# AnalogShield-03.net
KiCad netlist of a schematic drawn in EAGLE
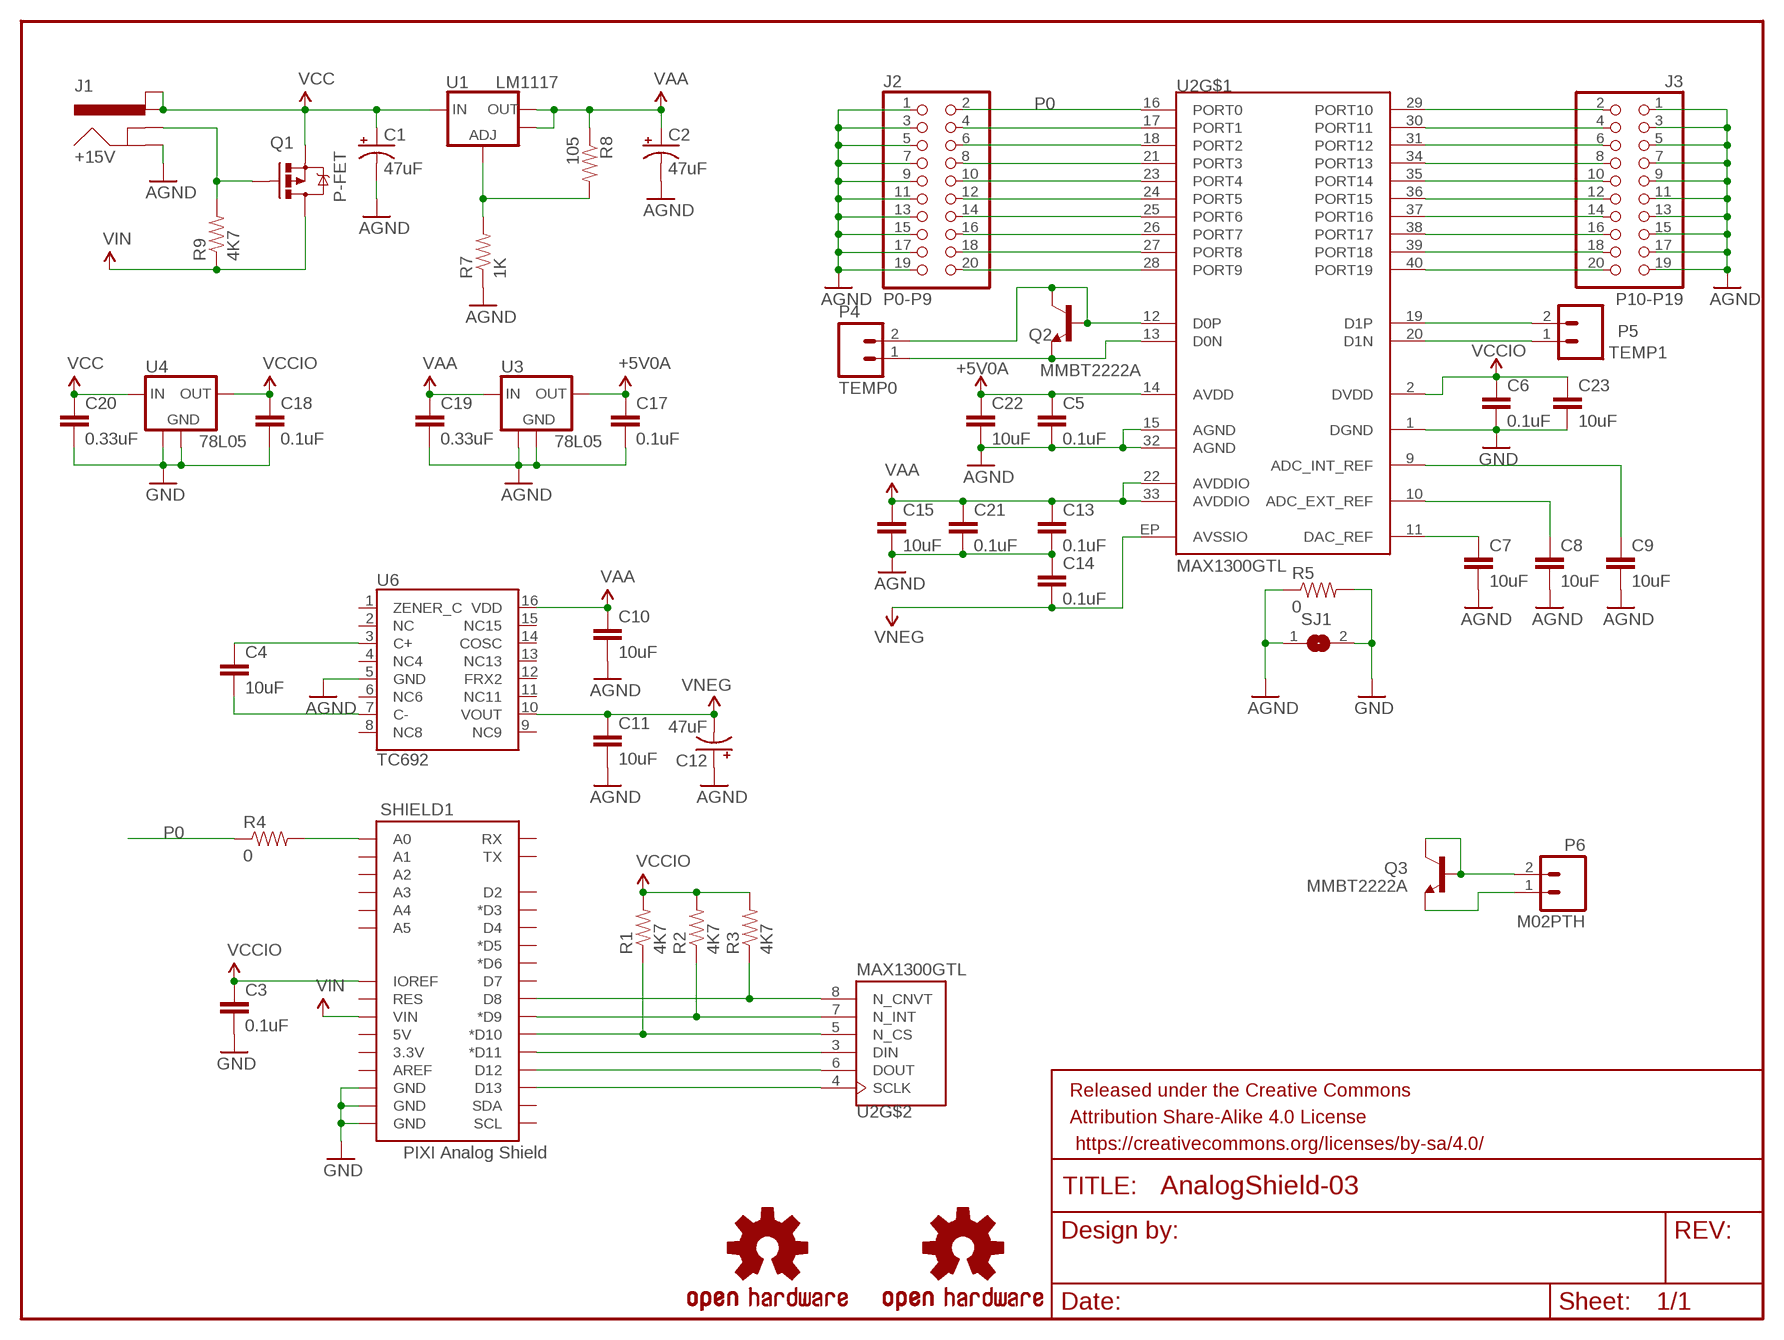
[diagram p0: schematic, sheet 1]

(export (version "E")
  (design (tool "Eeschema 10.0.6"))
  (components
    (comp (ref "C1")
      (value "47uF")
      (footprint "eagle-import:PANASONIC_D")
      (libsource (lib "eagle-import") (part "47UF-50V-20%(ELECT)"))
    )
    (comp (ref "C2")
      (value "47uF")
      (footprint "eagle-import:PANASONIC_D")
      (libsource (lib "eagle-import") (part "47UF-50V-20%(ELECT)"))
    )
    (comp (ref "C3")
      (value "0.1uF")
      (footprint "eagle-import:0603-CAP")
      (libsource (lib "eagle-import") (part "0.1UF-25V(+80/-20%)(0603)"))
    )
    (comp (ref "C4")
      (value "10uF")
      (footprint "eagle-import:1206")
      (libsource (lib "eagle-import") (part "10UF-25V-10%(1206)"))
    )
    (comp (ref "C5")
      (value "0.1uF")
      (footprint "eagle-import:0603-CAP")
      (libsource (lib "eagle-import") (part "0.1UF-25V(+80/-20%)(0603)"))
    )
    (comp (ref "C6")
      (value "0.1uF")
      (footprint "eagle-import:0603-CAP")
      (libsource (lib "eagle-import") (part "0.1UF-25V(+80/-20%)(0603)"))
    )
    (comp (ref "C7")
      (value "10uF")
      (footprint "eagle-import:1206")
      (libsource (lib "eagle-import") (part "10UF-25V-10%(1206)"))
    )
    (comp (ref "C8")
      (value "10uF")
      (footprint "eagle-import:1206")
      (libsource (lib "eagle-import") (part "10UF-25V-10%(1206)"))
    )
    (comp (ref "C9")
      (value "10uF")
      (footprint "eagle-import:1206")
      (libsource (lib "eagle-import") (part "10UF-25V-10%(1206)"))
    )
    (comp (ref "C10")
      (value "10uF")
      (footprint "eagle-import:1206")
      (libsource (lib "eagle-import") (part "10UF-25V-10%(1206)"))
    )
    (comp (ref "C11")
      (value "10uF")
      (footprint "eagle-import:1206")
      (libsource (lib "eagle-import") (part "10UF-25V-10%(1206)"))
    )
    (comp (ref "C12")
      (value "47uF")
      (footprint "eagle-import:PANASONIC_D")
      (libsource (lib "eagle-import") (part "47UF-50V-20%(ELECT)"))
    )
    (comp (ref "C13")
      (value "0.1uF")
      (footprint "eagle-import:0603-CAP")
      (libsource (lib "eagle-import") (part "0.1UF-25V(+80/-20%)(0603)"))
    )
    (comp (ref "C14")
      (value "0.1uF")
      (footprint "eagle-import:0603-CAP")
      (libsource (lib "eagle-import") (part "0.1UF-25V(+80/-20%)(0603)"))
    )
    (comp (ref "C15")
      (value "10uF")
      (footprint "eagle-import:1206")
      (libsource (lib "eagle-import") (part "10UF-25V-10%(1206)"))
    )
    (comp (ref "C17")
      (value "0.1uF")
      (footprint "eagle-import:0603-CAP")
      (libsource (lib "eagle-import") (part "0.1UF-25V(+80/-20%)(0603)"))
    )
    (comp (ref "C18")
      (value "0.1uF")
      (footprint "eagle-import:0603-CAP")
      (libsource (lib "eagle-import") (part "0.1UF-25V(+80/-20%)(0603)"))
    )
    (comp (ref "C19")
      (value "0.33uF")
      (footprint "eagle-import:0603-CAP")
      (libsource (lib "eagle-import") (part "0.33UF-25V(+20/-20%)(0603)"))
    )
    (comp (ref "C20")
      (value "0.33uF")
      (footprint "eagle-import:0603-CAP")
      (libsource (lib "eagle-import") (part "0.33UF-25V(+20/-20%)(0603)"))
    )
    (comp (ref "C21")
      (value "0.1uF")
      (footprint "eagle-import:0603-CAP")
      (libsource (lib "eagle-import") (part "0.1UF-25V(+80/-20%)(0603)"))
    )
    (comp (ref "C22")
      (value "10uF")
      (footprint "eagle-import:1206")
      (libsource (lib "eagle-import") (part "10UF-25V-10%(1206)"))
    )
    (comp (ref "C23")
      (value "10uF")
      (footprint "eagle-import:1206")
      (libsource (lib "eagle-import") (part "10UF-25V-10%(1206)"))
    )
    (comp (ref "FRAME1")
      (value "FRAME-LETTER")
      (footprint "eagle-import:CREATIVE_COMMONS")
      (libsource (lib "eagle-import") (part "FRAME-LETTER"))
    )
    (comp (ref "J1")
      (value "+15V")
      (footprint "eagle-import:POWER_JACK_SMD")
      (libsource (lib "eagle-import") (part "POWER_JACKSMD"))
    )
    (comp (ref "J2")
      (value "P0-P9")
      (footprint "eagle-import:2X10_SMD")
      (libsource (lib "eagle-import") (part "PINHD-2X10_SMD"))
    )
    (comp (ref "J3")
      (value "P10-P19")
      (footprint "eagle-import:2X10_SMD")
      (libsource (lib "eagle-import") (part "PINHD-2X10_SMD"))
    )
    (comp (ref "LOGO1")
      (value "OSHW-LOGOS")
      (footprint "eagle-import:OSHW-LOGO-S")
      (libsource (lib "eagle-import") (part "OSHW-LOGOS"))
    )
    (comp (ref "LOGO2")
      (value "OSHW-LOGOS")
      (footprint "eagle-import:OSHW-LOGO-S")
      (libsource (lib "eagle-import") (part "OSHW-LOGOS"))
    )
    (comp (ref "P4")
      (value "TEMP0")
      (footprint "eagle-import:1X02")
      (libsource (lib "eagle-import") (part "SparkFun-Connectors_M02PTH"))
    )
    (comp (ref "P5")
      (value "TEMP1")
      (footprint "eagle-import:JST-2-SMD-VERT")
      (libsource (lib "eagle-import") (part "M024UCON-15767"))
    )
    (comp (ref "P6")
      (value "M02PTH")
      (footprint "eagle-import:1X02")
      (libsource (lib "eagle-import") (part "SparkFun-Connectors_M02PTH"))
    )
    (comp (ref "Q1")
      (value "P-FET")
      (footprint "eagle-import:SOT23-3")
      (libsource (lib "eagle-import") (part "P-FET"))
    )
    (comp (ref "Q2")
      (value "MMBT2222A")
      (footprint "eagle-import:SOT23-3")
      (libsource (lib "eagle-import") (part "TRANSISTOR_NPNMMBT2222A"))
    )
    (comp (ref "Q3")
      (value "MMBT2222A")
      (footprint "eagle-import:SOT23-3")
      (libsource (lib "eagle-import") (part "TRANSISTOR_NPNMMBT2222A"))
    )
    (comp (ref "R1")
      (value "4K7")
      (footprint "eagle-import:0603")
      (libsource (lib "eagle-import") (part "4.7KOHM1/10W1%(0603)"))
    )
    (comp (ref "R2")
      (value "4K7")
      (footprint "eagle-import:0603")
      (libsource (lib "eagle-import") (part "4.7KOHM1/10W1%(0603)"))
    )
    (comp (ref "R3")
      (value "4K7")
      (footprint "eagle-import:0603")
      (libsource (lib "eagle-import") (part "4.7KOHM1/10W1%(0603)"))
    )
    (comp (ref "R4")
      (value "0")
      (footprint "eagle-import:0603")
      (libsource (lib "eagle-import") (part "0OHM-1/10W-5%(0603)"))
    )
    (comp (ref "R5")
      (value "0")
      (footprint "eagle-import:0603")
      (libsource (lib "eagle-import") (part "0OHM-1/10W-5%(0603)"))
    )
    (comp (ref "R7")
      (value "1K")
      (footprint "eagle-import:0603-RES")
      (libsource (lib "eagle-import") (part "1KOHM-1/10W-1%(0603)"))
    )
    (comp (ref "R8")
      (value "105")
      (footprint "eagle-import:0603-RES")
      (libsource (lib "eagle-import") (part "105OHM-1/10W-1%(0603)"))
    )
    (comp (ref "R9")
      (value "4K7")
      (footprint "eagle-import:0603")
      (libsource (lib "eagle-import") (part "4.7KOHM1/10W1%(0603)"))
    )
    (comp (ref "SHIELD1")
      (value "PIXI Analog Shield")
      (footprint "eagle-import:UNO_R3_SHIELD_NOLABELS")
      (libsource (lib "eagle-import") (part "ARDUINO_R3_SHIELDNOLABELS"))
    )
    (comp (ref "SJ1") (value "SJ") (footprint "eagle-import:SJ") (libsource (lib "eagle-import") (part "SJ")))
    (comp (ref "U1")
      (value "LM1117")
      (footprint "eagle-import:SOT223")
      (libsource (lib "eagle-import") (part "V_REG_LM1117SOT223"))
    )
    (comp (ref "U2")
      (value "MAX1300GTL")
      (footprint "eagle-import:QFN50P600X600X75-41")
      (fields (field (name "MFR1") "Maxim") (field (name "MFR1PN") "MAX11300GTL+"))
      (libsource (lib "eagle-import") (part "MAX11300GTL"))
    )
    (comp (ref "U3")
      (value "78L05")
      (footprint "eagle-import:SOT89")
      (libsource (lib "eagle-import") (part "78L05"))
    )
    (comp (ref "U4")
      (value "78L05")
      (footprint "eagle-import:SOT89")
      (libsource (lib "eagle-import") (part "78L05"))
    )
    (comp (ref "U6")
      (value "TC692")
      (footprint "eagle-import:SO16L")
      (libsource (lib "eagle-import") (part "TC962COE"))
    )
  )
  (nets
    (net (code "1") (name "+5V0A") (class "Default")
      (node (ref "C17") (pin "1") (pinfunction "1_1") (pintype "passive"))
      (node (ref "C22") (pin "1") (pinfunction "1_1") (pintype "passive"))
      (node (ref "C5") (pin "1") (pinfunction "1_1") (pintype "passive"))
      (node (ref "U2") (pin "14") (pinfunction "AVDD_14") (pintype "power_in"))
      (node (ref "U3") (pin "1") (pinfunction "OUT_1") (pintype "power_in"))
    )
    (net (code "2") (name "/P0") (class "Default")
      (node (ref "J2") (pin "2") (pinfunction "2_2") (pintype "passive"))
      (node (ref "R4") (pin "1") (pinfunction "1_1") (pintype "passive"))
      (node (ref "U2") (pin "16") (pinfunction "PORT0_16") (pintype "bidirectional"))
    )
    (net (code "3") (name "AGND") (class "Default")
      (node (ref "C1") (pin "-") (pinfunction "-_-") (pintype "passive"))
      (node (ref "C10") (pin "2") (pinfunction "2_2") (pintype "passive"))
      (node (ref "C11") (pin "2") (pinfunction "2_2") (pintype "passive"))
      (node (ref "C12") (pin "+") (pinfunction "+_+") (pintype "passive"))
      (node (ref "C13") (pin "2") (pinfunction "2_2") (pintype "passive"))
      (node (ref "C14") (pin "1") (pinfunction "1_1") (pintype "passive"))
      (node (ref "C15") (pin "2") (pinfunction "2_2") (pintype "passive"))
      (node (ref "C17") (pin "2") (pinfunction "2_2") (pintype "passive"))
      (node (ref "C19") (pin "2") (pinfunction "2_2") (pintype "passive"))
      (node (ref "C2") (pin "-") (pinfunction "-_-") (pintype "passive"))
      (node (ref "C21") (pin "2") (pinfunction "2_2") (pintype "passive"))
      (node (ref "C22") (pin "2") (pinfunction "2_2") (pintype "passive"))
      (node (ref "C5") (pin "2") (pinfunction "2_2") (pintype "passive"))
      (node (ref "C7") (pin "2") (pinfunction "2_2") (pintype "passive"))
      (node (ref "C8") (pin "2") (pinfunction "2_2") (pintype "passive"))
      (node (ref "C9") (pin "2") (pinfunction "2_2") (pintype "passive"))
      (node (ref "J1") (pin "GND") (pinfunction "GND_GND") (pintype "bidirectional"))
      (node (ref "J2") (pin "1") (pinfunction "1_1") (pintype "passive"))
      (node (ref "J2") (pin "11") (pinfunction "11_11") (pintype "passive"))
      (node (ref "J2") (pin "13") (pinfunction "13_13") (pintype "passive"))
      (node (ref "J2") (pin "15") (pinfunction "15_15") (pintype "passive"))
      (node (ref "J2") (pin "17") (pinfunction "17_17") (pintype "passive"))
      (node (ref "J2") (pin "19") (pinfunction "19_19") (pintype "passive"))
      (node (ref "J2") (pin "3") (pinfunction "3_3") (pintype "passive"))
      (node (ref "J2") (pin "5") (pinfunction "5_5") (pintype "passive"))
      (node (ref "J2") (pin "7") (pinfunction "7_7") (pintype "passive"))
      (node (ref "J2") (pin "9") (pinfunction "9_9") (pintype "passive"))
      (node (ref "J3") (pin "1") (pinfunction "1_1") (pintype "passive"))
      (node (ref "J3") (pin "11") (pinfunction "11_11") (pintype "passive"))
      (node (ref "J3") (pin "13") (pinfunction "13_13") (pintype "passive"))
      (node (ref "J3") (pin "15") (pinfunction "15_15") (pintype "passive"))
      (node (ref "J3") (pin "17") (pinfunction "17_17") (pintype "passive"))
      (node (ref "J3") (pin "19") (pinfunction "19_19") (pintype "passive"))
      (node (ref "J3") (pin "3") (pinfunction "3_3") (pintype "passive"))
      (node (ref "J3") (pin "5") (pinfunction "5_5") (pintype "passive"))
      (node (ref "J3") (pin "7") (pinfunction "7_7") (pintype "passive"))
      (node (ref "J3") (pin "9") (pinfunction "9_9") (pintype "passive"))
      (node (ref "R5") (pin "1") (pinfunction "1_1") (pintype "passive"))
      (node (ref "R7") (pin "1") (pinfunction "1_1") (pintype "passive"))
      (node (ref "SJ1") (pin "1") (pinfunction "1_1") (pintype "passive"))
      (node (ref "U2") (pin "15") (pinfunction "AGND_15") (pintype "power_in"))
      (node (ref "U2") (pin "32") (pinfunction "AGND_32") (pintype "power_in"))
      (node (ref "U3") (pin "2") (pinfunction "GND_2") (pintype "power_in"))
      (node (ref "U3") (pin "4") (pinfunction "GND_4") (pintype "power_in"))
      (node (ref "U6") (pin "5") (pinfunction "GND_5") (pintype "bidirectional"))
    )
    (net (code "4") (name "GND") (class "Default")
      (node (ref "C18") (pin "2") (pinfunction "2_2") (pintype "passive"))
      (node (ref "C20") (pin "2") (pinfunction "2_2") (pintype "passive"))
      (node (ref "C23") (pin "2") (pinfunction "2_2") (pintype "passive"))
      (node (ref "C3") (pin "2") (pinfunction "2_2") (pintype "passive"))
      (node (ref "C6") (pin "2") (pinfunction "2_2") (pintype "passive"))
      (node (ref "R5") (pin "2") (pinfunction "2_2") (pintype "passive"))
      (node (ref "SHIELD1") (pin "GND@0") (pinfunction "GND_GND@0") (pintype "bidirectional"))
      (node (ref "SHIELD1") (pin "GND@1") (pinfunction "GND_GND@1") (pintype "bidirectional"))
      (node (ref "SHIELD1") (pin "GND@2") (pinfunction "GND_GND@2") (pintype "bidirectional"))
      (node (ref "SJ1") (pin "2") (pinfunction "2_2") (pintype "passive"))
      (node (ref "U2") (pin "1") (pinfunction "DGND_1") (pintype "power_in"))
      (node (ref "U4") (pin "2") (pinfunction "GND_2") (pintype "power_in"))
      (node (ref "U4") (pin "4") (pinfunction "GND_4") (pintype "power_in"))
    )
    (net (code "5") (name "Net-(J1-GNDBREAK)") (class "Default")
      (node (ref "J1") (pin "P$4") (pinfunction "GNDBREAK_P$4") (pintype "bidirectional"))
      (node (ref "Q1") (pin "1") (pinfunction "G_1") (pintype "passive"))
      (node (ref "R9") (pin "2") (pinfunction "2_2") (pintype "passive"))
    )
    (net (code "6") (name "Net-(P5-1)") (class "Default")
      (node (ref "P5") (pin "2") (pinfunction "1_2") (pintype "passive"))
      (node (ref "U2") (pin "19") (pinfunction "D1P_19") (pintype "passive"))
    )
    (net (code "7") (name "Net-(P5-2)") (class "Default")
      (node (ref "P5") (pin "1") (pinfunction "2_1") (pintype "passive"))
      (node (ref "U2") (pin "20") (pinfunction "D1N_20") (pintype "passive"))
    )
    (net (code "8") (name "Net-(Q2-B)") (class "Default")
      (node (ref "P4") (pin "2") (pinfunction "2_2") (pintype "passive"))
      (node (ref "Q2") (pin "1") (pinfunction "B_1") (pintype "passive"))
      (node (ref "Q2") (pin "3") (pinfunction "C_3") (pintype "passive"))
      (node (ref "U2") (pin "12") (pinfunction "D0P_12") (pintype "passive"))
    )
    (net (code "9") (name "Net-(Q2-E)") (class "Default")
      (node (ref "P4") (pin "1") (pinfunction "1_1") (pintype "passive"))
      (node (ref "Q2") (pin "2") (pinfunction "E_2") (pintype "passive"))
      (node (ref "U2") (pin "13") (pinfunction "D0N_13") (pintype "passive"))
    )
    (net (code "10") (name "Net-(Q3-B)") (class "Default")
      (node (ref "P6") (pin "2") (pinfunction "2_2") (pintype "passive"))
      (node (ref "Q3") (pin "1") (pinfunction "B_1") (pintype "passive"))
      (node (ref "Q3") (pin "3") (pinfunction "C_3") (pintype "passive"))
    )
    (net (code "11") (name "Net-(Q3-E)") (class "Default")
      (node (ref "P6") (pin "1") (pinfunction "1_1") (pintype "passive"))
      (node (ref "Q3") (pin "2") (pinfunction "E_2") (pintype "passive"))
    )
    (net (code "12") (name "Net-(R4-Pad2)") (class "Default")
      (node (ref "R4") (pin "2") (pinfunction "2_2") (pintype "passive"))
      (node (ref "SHIELD1") (pin "A0") (pinfunction "A0_A0") (pintype "bidirectional"))
    )
    (net (code "13") (name "Net-(SHIELD1-*D9)") (class "Default")
      (node (ref "R2") (pin "1") (pinfunction "1_1") (pintype "passive"))
      (node (ref "SHIELD1") (pin "D9") (pinfunction "*D9_D9") (pintype "bidirectional"))
      (node (ref "U2") (pin "7") (pinfunction "N_INT_7") (pintype "output"))
    )
    (net (code "14") (name "Net-(SHIELD1-*D10)") (class "Default")
      (node (ref "R1") (pin "1") (pinfunction "1_1") (pintype "passive"))
      (node (ref "SHIELD1") (pin "D10") (pinfunction "*D10_D10") (pintype "bidirectional"))
      (node (ref "U2") (pin "5") (pinfunction "N_CS_5") (pintype "input"))
    )
    (net (code "15") (name "Net-(SHIELD1-*D11)") (class "Default")
      (node (ref "SHIELD1") (pin "D11") (pinfunction "*D11_D11") (pintype "bidirectional"))
      (node (ref "U2") (pin "3") (pinfunction "DIN_3") (pintype "input"))
    )
    (net (code "16") (name "Net-(U1-ADJ)") (class "Default")
      (node (ref "R7") (pin "2") (pinfunction "2_2") (pintype "passive"))
      (node (ref "R8") (pin "2") (pinfunction "2_2") (pintype "passive"))
      (node (ref "U1") (pin "1") (pinfunction "ADJ_1") (pintype "input"))
    )
    (net (code "17") (name "Net-(U2A-ADC_EXT_REF)") (class "Default")
      (node (ref "C8") (pin "1") (pinfunction "1_1") (pintype "passive"))
      (node (ref "U2") (pin "10") (pinfunction "ADC_EXT_REF_10") (pintype "passive"))
    )
    (net (code "18") (name "Net-(U2A-ADC_INT_REF)") (class "Default")
      (node (ref "C9") (pin "1") (pinfunction "1_1") (pintype "passive"))
      (node (ref "U2") (pin "9") (pinfunction "ADC_INT_REF_9") (pintype "passive"))
    )
    (net (code "19") (name "Net-(U2A-DAC_REF)") (class "Default")
      (node (ref "C7") (pin "1") (pinfunction "1_1") (pintype "passive"))
      (node (ref "U2") (pin "11") (pinfunction "DAC_REF_11") (pintype "passive"))
    )
    (net (code "20") (name "Net-(U2A-PORT1)") (class "Default")
      (node (ref "J2") (pin "4") (pinfunction "4_4") (pintype "passive"))
      (node (ref "U2") (pin "17") (pinfunction "PORT1_17") (pintype "bidirectional"))
    )
    (net (code "21") (name "Net-(U2A-PORT2)") (class "Default")
      (node (ref "J2") (pin "6") (pinfunction "6_6") (pintype "passive"))
      (node (ref "U2") (pin "18") (pinfunction "PORT2_18") (pintype "bidirectional"))
    )
    (net (code "22") (name "Net-(U2A-PORT3)") (class "Default")
      (node (ref "J2") (pin "8") (pinfunction "8_8") (pintype "passive"))
      (node (ref "U2") (pin "21") (pinfunction "PORT3_21") (pintype "bidirectional"))
    )
    (net (code "23") (name "Net-(U2A-PORT4)") (class "Default")
      (node (ref "J2") (pin "10") (pinfunction "10_10") (pintype "passive"))
      (node (ref "U2") (pin "23") (pinfunction "PORT4_23") (pintype "bidirectional"))
    )
    (net (code "24") (name "Net-(U2A-PORT5)") (class "Default")
      (node (ref "J2") (pin "12") (pinfunction "12_12") (pintype "passive"))
      (node (ref "U2") (pin "24") (pinfunction "PORT5_24") (pintype "bidirectional"))
    )
    (net (code "25") (name "Net-(U2A-PORT6)") (class "Default")
      (node (ref "J2") (pin "14") (pinfunction "14_14") (pintype "passive"))
      (node (ref "U2") (pin "25") (pinfunction "PORT6_25") (pintype "bidirectional"))
    )
    (net (code "26") (name "Net-(U2A-PORT7)") (class "Default")
      (node (ref "J2") (pin "16") (pinfunction "16_16") (pintype "passive"))
      (node (ref "U2") (pin "26") (pinfunction "PORT7_26") (pintype "bidirectional"))
    )
    (net (code "27") (name "Net-(U2A-PORT8)") (class "Default")
      (node (ref "J2") (pin "18") (pinfunction "18_18") (pintype "passive"))
      (node (ref "U2") (pin "27") (pinfunction "PORT8_27") (pintype "bidirectional"))
    )
    (net (code "28") (name "Net-(U2A-PORT9)") (class "Default")
      (node (ref "J2") (pin "20") (pinfunction "20_20") (pintype "passive"))
      (node (ref "U2") (pin "28") (pinfunction "PORT9_28") (pintype "bidirectional"))
    )
    (net (code "29") (name "Net-(U2A-PORT10)") (class "Default")
      (node (ref "J3") (pin "2") (pinfunction "2_2") (pintype "passive"))
      (node (ref "U2") (pin "29") (pinfunction "PORT10_29") (pintype "bidirectional"))
    )
    (net (code "30") (name "Net-(U2A-PORT11)") (class "Default")
      (node (ref "J3") (pin "4") (pinfunction "4_4") (pintype "passive"))
      (node (ref "U2") (pin "30") (pinfunction "PORT11_30") (pintype "bidirectional"))
    )
    (net (code "31") (name "Net-(U2A-PORT12)") (class "Default")
      (node (ref "J3") (pin "6") (pinfunction "6_6") (pintype "passive"))
      (node (ref "U2") (pin "31") (pinfunction "PORT12_31") (pintype "bidirectional"))
    )
    (net (code "32") (name "Net-(U2A-PORT13)") (class "Default")
      (node (ref "J3") (pin "8") (pinfunction "8_8") (pintype "passive"))
      (node (ref "U2") (pin "34") (pinfunction "PORT13_34") (pintype "bidirectional"))
    )
    (net (code "33") (name "Net-(U2A-PORT14)") (class "Default")
      (node (ref "J3") (pin "10") (pinfunction "10_10") (pintype "passive"))
      (node (ref "U2") (pin "35") (pinfunction "PORT14_35") (pintype "bidirectional"))
    )
    (net (code "34") (name "Net-(U2A-PORT15)") (class "Default")
      (node (ref "J3") (pin "12") (pinfunction "12_12") (pintype "passive"))
      (node (ref "U2") (pin "36") (pinfunction "PORT15_36") (pintype "bidirectional"))
    )
    (net (code "35") (name "Net-(U2A-PORT16)") (class "Default")
      (node (ref "J3") (pin "14") (pinfunction "14_14") (pintype "passive"))
      (node (ref "U2") (pin "37") (pinfunction "PORT16_37") (pintype "bidirectional"))
    )
    (net (code "36") (name "Net-(U2A-PORT17)") (class "Default")
      (node (ref "J3") (pin "16") (pinfunction "16_16") (pintype "passive"))
      (node (ref "U2") (pin "38") (pinfunction "PORT17_38") (pintype "bidirectional"))
    )
    (net (code "37") (name "Net-(U2A-PORT18)") (class "Default")
      (node (ref "J3") (pin "18") (pinfunction "18_18") (pintype "passive"))
      (node (ref "U2") (pin "39") (pinfunction "PORT18_39") (pintype "bidirectional"))
    )
    (net (code "38") (name "Net-(U2A-PORT19)") (class "Default")
      (node (ref "J3") (pin "20") (pinfunction "20_20") (pintype "passive"))
      (node (ref "U2") (pin "40") (pinfunction "PORT19_40") (pintype "bidirectional"))
    )
    (net (code "39") (name "Net-(U2B-DOUT)") (class "Default")
      (node (ref "SHIELD1") (pin "D12") (pinfunction "D12_D12") (pintype "bidirectional"))
      (node (ref "U2") (pin "6") (pinfunction "DOUT_6") (pintype "output"))
    )
    (net (code "40") (name "Net-(U2B-N_CNVT)") (class "Default")
      (node (ref "R3") (pin "1") (pinfunction "1_1") (pintype "passive"))
      (node (ref "SHIELD1") (pin "D8") (pinfunction "D8_D8") (pintype "bidirectional"))
      (node (ref "U2") (pin "8") (pinfunction "N_CNVT_8") (pintype "input"))
    )
    (net (code "41") (name "Net-(U2B-SCLK)") (class "Default")
      (node (ref "SHIELD1") (pin "D13") (pinfunction "D13_D13") (pintype "bidirectional"))
      (node (ref "U2") (pin "4") (pinfunction "SCLK_4") (pintype "input"))
    )
    (net (code "42") (name "Net-(U6-C+)") (class "Default")
      (node (ref "C4") (pin "1") (pinfunction "1_1") (pintype "passive"))
      (node (ref "U6") (pin "3") (pinfunction "C+_3") (pintype "bidirectional"))
    )
    (net (code "43") (name "Net-(U6-C-)") (class "Default")
      (node (ref "C4") (pin "2") (pinfunction "2_2") (pintype "passive"))
      (node (ref "U6") (pin "7") (pinfunction "C-_7") (pintype "bidirectional"))
    )
    (net (code "44") (name "VAA") (class "Default")
      (node (ref "C10") (pin "1") (pinfunction "1_1") (pintype "passive"))
      (node (ref "C13") (pin "1") (pinfunction "1_1") (pintype "passive"))
      (node (ref "C15") (pin "1") (pinfunction "1_1") (pintype "passive"))
      (node (ref "C19") (pin "1") (pinfunction "1_1") (pintype "passive"))
      (node (ref "C2") (pin "+") (pinfunction "+_+") (pintype "passive"))
      (node (ref "C21") (pin "1") (pinfunction "1_1") (pintype "passive"))
      (node (ref "R8") (pin "1") (pinfunction "1_1") (pintype "passive"))
      (node (ref "U1") (pin "2") (pinfunction "OUT_2") (pintype "power_in"))
      (node (ref "U1") (pin "4") (pinfunction "OUT_4") (pintype "power_in"))
      (node (ref "U2") (pin "22") (pinfunction "AVDDIO_22") (pintype "power_in"))
      (node (ref "U2") (pin "33") (pinfunction "AVDDIO_33") (pintype "power_in"))
      (node (ref "U3") (pin "3") (pinfunction "IN_3") (pintype "input"))
      (node (ref "U6") (pin "16") (pinfunction "VDD_16") (pintype "bidirectional"))
    )
    (net (code "45") (name "VCC") (class "Default")
      (node (ref "C1") (pin "+") (pinfunction "+_+") (pintype "passive"))
      (node (ref "C20") (pin "1") (pinfunction "1_1") (pintype "passive"))
      (node (ref "J1") (pin "VIN0$1") (pinfunction "PWR_VIN0$1") (pintype "bidirectional"))
      (node (ref "J1") (pin "VIN0$2") (pinfunction "PWR1_VIN0$2") (pintype "bidirectional"))
      (node (ref "Q1") (pin "2") (pinfunction "S_2") (pintype "passive"))
      (node (ref "U1") (pin "3") (pinfunction "IN_3") (pintype "input"))
      (node (ref "U4") (pin "3") (pinfunction "IN_3") (pintype "input"))
    )
    (net (code "46") (name "VCCIO") (class "Default")
      (node (ref "C18") (pin "1") (pinfunction "1_1") (pintype "passive"))
      (node (ref "C23") (pin "1") (pinfunction "1_1") (pintype "passive"))
      (node (ref "C3") (pin "1") (pinfunction "1_1") (pintype "passive"))
      (node (ref "C6") (pin "1") (pinfunction "1_1") (pintype "passive"))
      (node (ref "R1") (pin "2") (pinfunction "2_2") (pintype "passive"))
      (node (ref "R2") (pin "2") (pinfunction "2_2") (pintype "passive"))
      (node (ref "R3") (pin "2") (pinfunction "2_2") (pintype "passive"))
      (node (ref "SHIELD1") (pin "IOREF") (pinfunction "IOREF_IOREF") (pintype "bidirectional"))
      (node (ref "U2") (pin "2") (pinfunction "DVDD_2") (pintype "power_in"))
      (node (ref "U4") (pin "1") (pinfunction "OUT_1") (pintype "power_in"))
    )
    (net (code "47") (name "VIN") (class "Default")
      (node (ref "Q1") (pin "3") (pinfunction "D_3") (pintype "passive"))
      (node (ref "R9") (pin "1") (pinfunction "1_1") (pintype "passive"))
      (node (ref "SHIELD1") (pin "VIN") (pinfunction "VIN_VIN") (pintype "bidirectional"))
    )
    (net (code "48") (name "VNEG") (class "Default")
      (node (ref "C11") (pin "1") (pinfunction "1_1") (pintype "passive"))
      (node (ref "C12") (pin "-") (pinfunction "-_-") (pintype "passive"))
      (node (ref "C14") (pin "2") (pinfunction "2_2") (pintype "passive"))
      (node (ref "U2") (pin "EP") (pinfunction "AVSSIO_EP") (pintype "power_in"))
      (node (ref "U6") (pin "10") (pinfunction "VOUT_10") (pintype "bidirectional"))
    )
    (net (code "49") (name "unconnected-(SHIELD1-*D3-PadD3)") (class "Default")
      (node (ref "SHIELD1") (pin "D3") (pinfunction "*D3_D3") (pintype "bidirectional"))
    )
    (net (code "50") (name "unconnected-(SHIELD1-*D5-PadD5)") (class "Default")
      (node (ref "SHIELD1") (pin "D5") (pinfunction "*D5_D5") (pintype "bidirectional"))
    )
    (net (code "51") (name "unconnected-(SHIELD1-*D6-PadD6)") (class "Default")
      (node (ref "SHIELD1") (pin "D6") (pinfunction "*D6_D6") (pintype "bidirectional"))
    )
    (net (code "52") (name "unconnected-(SHIELD1-Pad3.3V)") (class "Default")
      (node (ref "SHIELD1") (pin "3.3V") (pinfunction "3.3V_3.3V") (pintype "bidirectional"))
    )
    (net (code "53") (name "unconnected-(SHIELD1-Pad5V)") (class "Default")
      (node (ref "SHIELD1") (pin "5V") (pinfunction "5V_5V") (pintype "bidirectional"))
    )
    (net (code "54") (name "unconnected-(SHIELD1-PadA1)") (class "Default")
      (node (ref "SHIELD1") (pin "A1") (pinfunction "A1_A1") (pintype "bidirectional"))
    )
    (net (code "55") (name "unconnected-(SHIELD1-PadA2)") (class "Default")
      (node (ref "SHIELD1") (pin "A2") (pinfunction "A2_A2") (pintype "bidirectional"))
    )
    (net (code "56") (name "unconnected-(SHIELD1-PadA3)") (class "Default")
      (node (ref "SHIELD1") (pin "A3") (pinfunction "A3_A3") (pintype "bidirectional"))
    )
    (net (code "57") (name "unconnected-(SHIELD1-PadA4)") (class "Default")
      (node (ref "SHIELD1") (pin "A4") (pinfunction "A4_A4") (pintype "bidirectional"))
    )
    (net (code "58") (name "unconnected-(SHIELD1-PadA5)") (class "Default")
      (node (ref "SHIELD1") (pin "A5") (pinfunction "A5_A5") (pintype "bidirectional"))
    )
    (net (code "59") (name "unconnected-(SHIELD1-PadAREF)") (class "Default")
      (node (ref "SHIELD1") (pin "AREF") (pinfunction "AREF_AREF") (pintype "bidirectional"))
    )
    (net (code "60") (name "unconnected-(SHIELD1-PadD2)") (class "Default")
      (node (ref "SHIELD1") (pin "D2") (pinfunction "D2_D2") (pintype "bidirectional"))
    )
    (net (code "61") (name "unconnected-(SHIELD1-PadD4)") (class "Default")
      (node (ref "SHIELD1") (pin "D4") (pinfunction "D4_D4") (pintype "bidirectional"))
    )
    (net (code "62") (name "unconnected-(SHIELD1-PadD7)") (class "Default")
      (node (ref "SHIELD1") (pin "D7") (pinfunction "D7_D7") (pintype "bidirectional"))
    )
    (net (code "63") (name "unconnected-(SHIELD1-PadRES)") (class "Default")
      (node (ref "SHIELD1") (pin "RES") (pinfunction "RES_RES") (pintype "bidirectional"))
    )
    (net (code "64") (name "unconnected-(SHIELD1-PadRX)") (class "Default")
      (node (ref "SHIELD1") (pin "RX") (pinfunction "RX_RX") (pintype "bidirectional"))
    )
    (net (code "65") (name "unconnected-(SHIELD1-PadSCL)") (class "Default")
      (node (ref "SHIELD1") (pin "SCL") (pinfunction "SCL_SCL") (pintype "bidirectional"))
    )
    (net (code "66") (name "unconnected-(SHIELD1-PadSDA)") (class "Default")
      (node (ref "SHIELD1") (pin "SDA") (pinfunction "SDA_SDA") (pintype "bidirectional"))
    )
    (net (code "67") (name "unconnected-(SHIELD1-PadTX)") (class "Default")
      (node (ref "SHIELD1") (pin "TX") (pinfunction "TX_TX") (pintype "bidirectional"))
    )
    (net (code "68") (name "unconnected-(U6-COSC-Pad14)") (class "Default")
      (node (ref "U6") (pin "14") (pinfunction "COSC_14") (pintype "bidirectional"))
    )
    (net (code "69") (name "unconnected-(U6-FRX2-Pad12)") (class "Default")
      (node (ref "U6") (pin "12") (pinfunction "FRX2_12") (pintype "bidirectional"))
    )
    (net (code "70") (name "unconnected-(U6-NC-Pad2)") (class "Default")
      (node (ref "U6") (pin "2") (pinfunction "NC_2") (pintype "bidirectional"))
    )
    (net (code "71") (name "unconnected-(U6-NC4-Pad4)") (class "Default")
      (node (ref "U6") (pin "4") (pinfunction "NC4_4") (pintype "bidirectional"))
    )
    (net (code "72") (name "unconnected-(U6-NC6-Pad6)") (class "Default")
      (node (ref "U6") (pin "6") (pinfunction "NC6_6") (pintype "bidirectional"))
    )
    (net (code "73") (name "unconnected-(U6-NC8-Pad8)") (class "Default")
      (node (ref "U6") (pin "8") (pinfunction "NC8_8") (pintype "bidirectional"))
    )
    (net (code "74") (name "unconnected-(U6-NC9-Pad9)") (class "Default")
      (node (ref "U6") (pin "9") (pinfunction "NC9_9") (pintype "bidirectional"))
    )
    (net (code "75") (name "unconnected-(U6-NC11-Pad11)") (class "Default")
      (node (ref "U6") (pin "11") (pinfunction "NC11_11") (pintype "bidirectional"))
    )
    (net (code "76") (name "unconnected-(U6-NC13-Pad13)") (class "Default")
      (node (ref "U6") (pin "13") (pinfunction "NC13_13") (pintype "bidirectional"))
    )
    (net (code "77") (name "unconnected-(U6-NC15-Pad15)") (class "Default")
      (node (ref "U6") (pin "15") (pinfunction "NC15_15") (pintype "bidirectional"))
    )
    (net (code "78") (name "unconnected-(U6-ZENER_C-Pad1)") (class "Default")
      (node (ref "U6") (pin "1") (pinfunction "ZENER_C_1") (pintype "bidirectional"))
    )
  )
)
